# ESP12_mosfet_1117.net
KiCad netlist of a schematic drawn in EAGLE
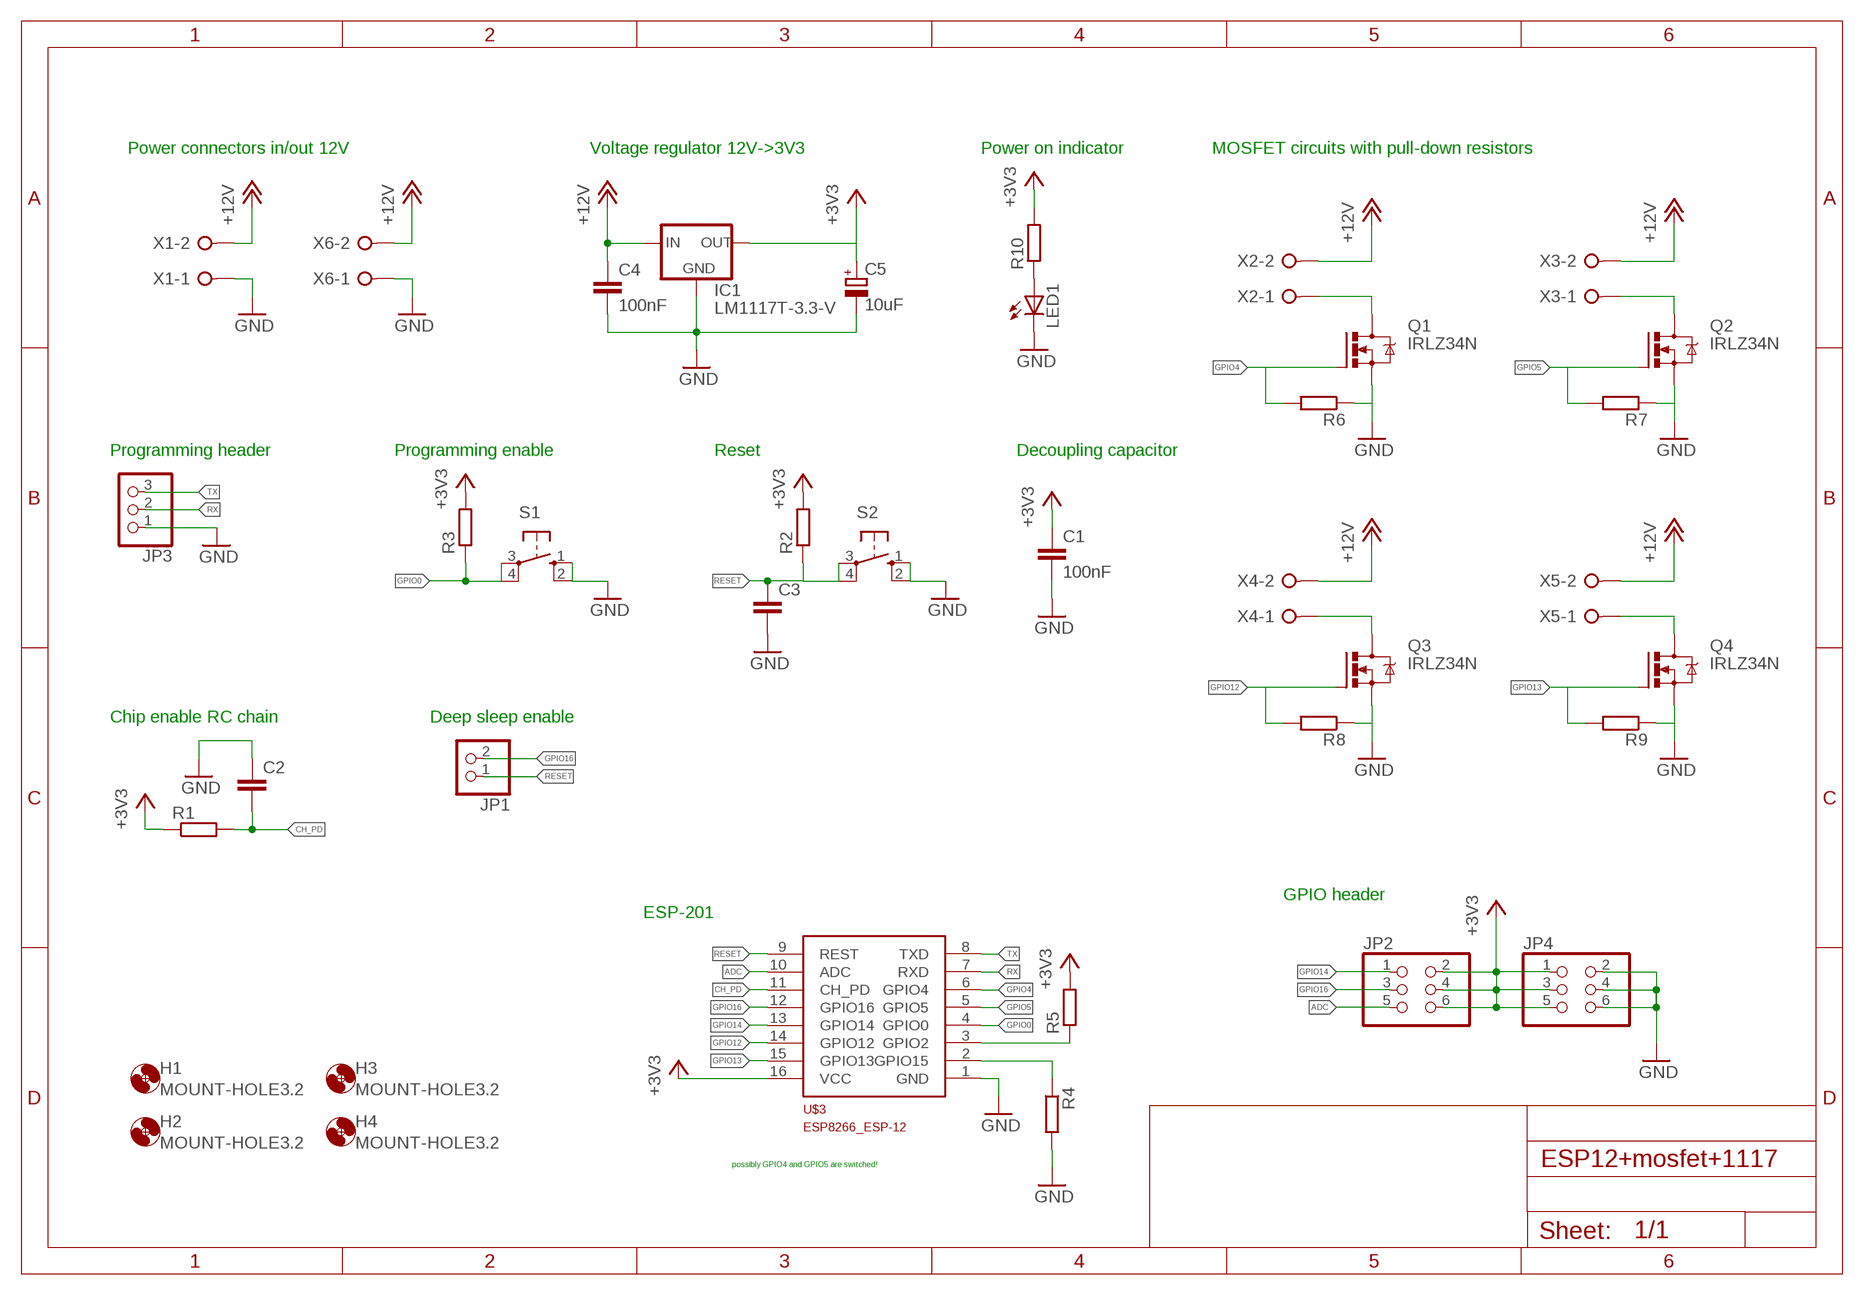
[diagram p0: schematic, sheet 1]

(export (version "E")
  (design (tool "Eeschema 10.0.6"))
  (components
    (comp (ref "C1")
      (value "100nF")
      (footprint "eagle-import:C0805")
      (libsource (lib "eagle-import") (part "C-EUC0805"))
    )
    (comp (ref "C2")
      (value "C-EUC0805")
      (footprint "eagle-import:C0805")
      (libsource (lib "eagle-import") (part "C-EUC0805"))
    )
    (comp (ref "C3")
      (value "C-EUC0805")
      (footprint "eagle-import:C0805")
      (libsource (lib "eagle-import") (part "C-EUC0805"))
    )
    (comp (ref "C4")
      (value "100nF")
      (footprint "eagle-import:C0805")
      (libsource (lib "eagle-import") (part "C-EUC0805"))
    )
    (comp (ref "C5")
      (value "10uF")
      (footprint "eagle-import:E2-4")
      (libsource (lib "eagle-import") (part "CPOL-EUE2-4"))
    )
    (comp (ref "H1")
      (value "MOUNT-HOLE3.2")
      (footprint "eagle-import:3,2")
      (libsource (lib "eagle-import") (part "MOUNT-HOLE3.2"))
    )
    (comp (ref "H2")
      (value "MOUNT-HOLE3.2")
      (footprint "eagle-import:3,2")
      (libsource (lib "eagle-import") (part "MOUNT-HOLE3.2"))
    )
    (comp (ref "H3")
      (value "MOUNT-HOLE3.2")
      (footprint "eagle-import:3,2")
      (libsource (lib "eagle-import") (part "MOUNT-HOLE3.2"))
    )
    (comp (ref "H4")
      (value "MOUNT-HOLE3.2")
      (footprint "eagle-import:3,2")
      (libsource (lib "eagle-import") (part "MOUNT-HOLE3.2"))
    )
    (comp (ref "IC1")
      (value "LM1117T-3.3-V")
      (footprint "eagle-import:TO220V")
      (libsource (lib "eagle-import") (part "LM1117T--V3.3"))
    )
    (comp (ref "JP1")
      (value "PINHD-1X2")
      (footprint "eagle-import:1X02")
      (libsource (lib "eagle-import") (part "PINHD-1X2"))
    )
    (comp (ref "JP2")
      (value "PINHD-2X3")
      (footprint "eagle-import:2X03")
      (libsource (lib "eagle-import") (part "PINHD-2X3"))
    )
    (comp (ref "JP3")
      (value "PINHD-1X3")
      (footprint "eagle-import:1X03")
      (libsource (lib "eagle-import") (part "PINHD-1X3"))
    )
    (comp (ref "JP4")
      (value "PINHD-2X3")
      (footprint "eagle-import:2X03")
      (libsource (lib "eagle-import") (part "PINHD-2X3"))
    )
    (comp (ref "LED1")
      (value "LED3MM")
      (footprint "eagle-import:LED3MM")
      (libsource (lib "eagle-import") (part "LED3MM"))
    )
    (comp (ref "Q1")
      (value "IRLZ34N")
      (footprint "eagle-import:TO220BV")
      (libsource (lib "eagle-import") (part "IRLZ44ZTO220BV"))
    )
    (comp (ref "Q2")
      (value "IRLZ34N")
      (footprint "eagle-import:TO220BV")
      (libsource (lib "eagle-import") (part "IRLZ44ZTO220BV"))
    )
    (comp (ref "Q3")
      (value "IRLZ34N")
      (footprint "eagle-import:TO220BV")
      (libsource (lib "eagle-import") (part "IRLZ44ZTO220BV"))
    )
    (comp (ref "Q4")
      (value "IRLZ34N")
      (footprint "eagle-import:TO220BV")
      (libsource (lib "eagle-import") (part "IRLZ44ZTO220BV"))
    )
    (comp (ref "R1")
      (value "R-EU_R0805")
      (footprint "eagle-import:R0805")
      (libsource (lib "eagle-import") (part "R-EU_R0805"))
    )
    (comp (ref "R2")
      (value "R-EU_R0805")
      (footprint "eagle-import:R0805")
      (libsource (lib "eagle-import") (part "R-EU_R0805"))
    )
    (comp (ref "R3")
      (value "R-EU_R0805")
      (footprint "eagle-import:R0805")
      (libsource (lib "eagle-import") (part "R-EU_R0805"))
    )
    (comp (ref "R4")
      (value "R-EU_R0805")
      (footprint "eagle-import:R0805")
      (libsource (lib "eagle-import") (part "R-EU_R0805"))
    )
    (comp (ref "R5")
      (value "R-EU_R0805")
      (footprint "eagle-import:R0805")
      (libsource (lib "eagle-import") (part "R-EU_R0805"))
    )
    (comp (ref "R6")
      (value "R-EU_R0805")
      (footprint "eagle-import:R0805")
      (libsource (lib "eagle-import") (part "R-EU_R0805"))
    )
    (comp (ref "R7")
      (value "R-EU_R0805")
      (footprint "eagle-import:R0805")
      (libsource (lib "eagle-import") (part "R-EU_R0805"))
    )
    (comp (ref "R8")
      (value "R-EU_R0805")
      (footprint "eagle-import:R0805")
      (libsource (lib "eagle-import") (part "R-EU_R0805"))
    )
    (comp (ref "R9")
      (value "R-EU_R0805")
      (footprint "eagle-import:R0805")
      (libsource (lib "eagle-import") (part "R-EU_R0805"))
    )
    (comp (ref "R10")
      (value "R-EU_0207/10")
      (footprint "eagle-import:0207_10")
      (libsource (lib "eagle-import") (part "R-EU_0207/10"))
    )
    (comp (ref "S1")
      (value "10-XX")
      (footprint "eagle-import:B3F-10XX")
      (fields (field (name "MPN") "B3F-1000"))
      (libsource (lib "eagle-import") (part "10-XX"))
    )
    (comp (ref "S2")
      (value "10-XX")
      (footprint "eagle-import:B3F-10XX")
      (fields (field (name "MPN") "B3F-1000"))
      (libsource (lib "eagle-import") (part "10-XX"))
    )
    (comp (ref "U$3")
      (value "ESP8266_ESP-12")
      (footprint "eagle-import:ESP8266-ESP12")
      (libsource (lib "eagle-import") (part "ESP8266_ESP-12"))
    )
    (comp (ref "X1")
      (value "W237-02P")
      (footprint "eagle-import:W237-132")
      (libsource (lib "eagle-import") (part "W237-02P"))
    )
    (comp (ref "X2")
      (value "W237-02P")
      (footprint "eagle-import:W237-132")
      (libsource (lib "eagle-import") (part "W237-02P"))
    )
    (comp (ref "X3")
      (value "W237-02P")
      (footprint "eagle-import:W237-132")
      (libsource (lib "eagle-import") (part "W237-02P"))
    )
    (comp (ref "X4")
      (value "W237-02P")
      (footprint "eagle-import:W237-132")
      (libsource (lib "eagle-import") (part "W237-02P"))
    )
    (comp (ref "X5")
      (value "W237-02P")
      (footprint "eagle-import:W237-132")
      (libsource (lib "eagle-import") (part "W237-02P"))
    )
    (comp (ref "X6")
      (value "W237-02P")
      (footprint "eagle-import:W237-132")
      (libsource (lib "eagle-import") (part "W237-02P"))
    )
  )
  (nets
    (net (code "1") (name "+3V3") (class "Default")
      (node (ref "C1") (pin "1") (pinfunction "1_1") (pintype "passive"))
      (node (ref "C5") (pin "+") (pinfunction "+_+") (pintype "passive"))
      (node (ref "IC1") (pin "2") (pinfunction "OUT_2") (pintype "passive"))
      (node (ref "JP2") (pin "2") (pinfunction "2_2") (pintype "passive"))
      (node (ref "JP2") (pin "4") (pinfunction "4_4") (pintype "passive"))
      (node (ref "JP2") (pin "6") (pinfunction "6_6") (pintype "passive"))
      (node (ref "JP4") (pin "1") (pinfunction "1_1") (pintype "passive"))
      (node (ref "JP4") (pin "3") (pinfunction "3_3") (pintype "passive"))
      (node (ref "JP4") (pin "5") (pinfunction "5_5") (pintype "passive"))
      (node (ref "R1") (pin "1") (pinfunction "1_1") (pintype "passive"))
      (node (ref "R10") (pin "2") (pinfunction "2_2") (pintype "passive"))
      (node (ref "R2") (pin "2") (pinfunction "2_2") (pintype "passive"))
      (node (ref "R3") (pin "2") (pinfunction "2_2") (pintype "passive"))
      (node (ref "R5") (pin "2") (pinfunction "2_2") (pintype "passive"))
      (node (ref "U$3") (pin "16") (pinfunction "VCC_16") (pintype "bidirectional"))
    )
    (net (code "2") (name "+12V") (class "Default")
      (node (ref "C4") (pin "1") (pinfunction "1_1") (pintype "passive"))
      (node (ref "IC1") (pin "3") (pinfunction "IN_3") (pintype "input"))
      (node (ref "X1") (pin "2") (pinfunction "KL_2") (pintype "passive"))
      (node (ref "X2") (pin "2") (pinfunction "KL_2") (pintype "passive"))
      (node (ref "X3") (pin "2") (pinfunction "KL_2") (pintype "passive"))
      (node (ref "X4") (pin "2") (pinfunction "KL_2") (pintype "passive"))
      (node (ref "X5") (pin "2") (pinfunction "KL_2") (pintype "passive"))
      (node (ref "X6") (pin "2") (pinfunction "KL_2") (pintype "passive"))
    )
    (net (code "3") (name "ADC") (class "Default")
      (node (ref "JP2") (pin "5") (pinfunction "5_5") (pintype "passive"))
      (node (ref "U$3") (pin "10") (pinfunction "ADC_10") (pintype "bidirectional"))
    )
    (net (code "4") (name "CH_PD") (class "Default")
      (node (ref "C2") (pin "2") (pinfunction "2_2") (pintype "passive"))
      (node (ref "R1") (pin "2") (pinfunction "2_2") (pintype "passive"))
      (node (ref "U$3") (pin "11") (pinfunction "CH_PD_11") (pintype "bidirectional"))
    )
    (net (code "5") (name "GND") (class "Default")
      (node (ref "C1") (pin "2") (pinfunction "2_2") (pintype "passive"))
      (node (ref "C2") (pin "1") (pinfunction "1_1") (pintype "passive"))
      (node (ref "C3") (pin "2") (pinfunction "2_2") (pintype "passive"))
      (node (ref "C4") (pin "2") (pinfunction "2_2") (pintype "passive"))
      (node (ref "C5") (pin "-") (pinfunction "-_-") (pintype "passive"))
      (node (ref "IC1") (pin "1") (pinfunction "GND_1") (pintype "input"))
      (node (ref "JP3") (pin "1") (pinfunction "1_1") (pintype "passive"))
      (node (ref "JP4") (pin "2") (pinfunction "2_2") (pintype "passive"))
      (node (ref "JP4") (pin "4") (pinfunction "4_4") (pintype "passive"))
      (node (ref "JP4") (pin "6") (pinfunction "6_6") (pintype "passive"))
      (node (ref "LED1") (pin "K") (pinfunction "C_K") (pintype "passive"))
      (node (ref "Q1") (pin "S") (pinfunction "S_S") (pintype "passive"))
      (node (ref "Q2") (pin "S") (pinfunction "S_S") (pintype "passive"))
      (node (ref "Q3") (pin "S") (pinfunction "S_S") (pintype "passive"))
      (node (ref "Q4") (pin "S") (pinfunction "S_S") (pintype "passive"))
      (node (ref "R4") (pin "2") (pinfunction "2_2") (pintype "passive"))
      (node (ref "R6") (pin "1") (pinfunction "1_1") (pintype "passive"))
      (node (ref "R7") (pin "1") (pinfunction "1_1") (pintype "passive"))
      (node (ref "R8") (pin "1") (pinfunction "1_1") (pintype "passive"))
      (node (ref "R9") (pin "1") (pinfunction "1_1") (pintype "passive"))
      (node (ref "S1") (pin "1") (pinfunction "S_1") (pintype "passive"))
      (node (ref "S1") (pin "2") (pinfunction "S1_2") (pintype "passive"))
      (node (ref "S2") (pin "1") (pinfunction "S_1") (pintype "passive"))
      (node (ref "S2") (pin "2") (pinfunction "S1_2") (pintype "passive"))
      (node (ref "U$3") (pin "1") (pinfunction "GND_1") (pintype "bidirectional"))
      (node (ref "X1") (pin "1") (pinfunction "KL_1") (pintype "passive"))
      (node (ref "X6") (pin "1") (pinfunction "KL_1") (pintype "passive"))
    )
    (net (code "6") (name "GPIO0") (class "Default")
      (node (ref "R3") (pin "1") (pinfunction "1_1") (pintype "passive"))
      (node (ref "S1") (pin "3") (pinfunction "P_3") (pintype "passive"))
      (node (ref "S1") (pin "4") (pinfunction "P1_4") (pintype "passive"))
      (node (ref "U$3") (pin "4") (pinfunction "GPIO0_4") (pintype "bidirectional"))
    )
    (net (code "7") (name "GPIO4") (class "Default")
      (node (ref "Q1") (pin "G") (pinfunction "G_G") (pintype "passive"))
      (node (ref "R6") (pin "2") (pinfunction "2_2") (pintype "passive"))
      (node (ref "U$3") (pin "6") (pinfunction "GPIO4_6") (pintype "bidirectional"))
    )
    (net (code "8") (name "GPIO5") (class "Default")
      (node (ref "Q2") (pin "G") (pinfunction "G_G") (pintype "passive"))
      (node (ref "R7") (pin "2") (pinfunction "2_2") (pintype "passive"))
      (node (ref "U$3") (pin "5") (pinfunction "GPIO5_5") (pintype "bidirectional"))
    )
    (net (code "9") (name "GPIO12") (class "Default")
      (node (ref "Q3") (pin "G") (pinfunction "G_G") (pintype "passive"))
      (node (ref "R8") (pin "2") (pinfunction "2_2") (pintype "passive"))
      (node (ref "U$3") (pin "14") (pinfunction "GPIO12_14") (pintype "bidirectional"))
    )
    (net (code "10") (name "GPIO13") (class "Default")
      (node (ref "Q4") (pin "G") (pinfunction "G_G") (pintype "passive"))
      (node (ref "R9") (pin "2") (pinfunction "2_2") (pintype "passive"))
      (node (ref "U$3") (pin "15") (pinfunction "GPIO13_15") (pintype "bidirectional"))
    )
    (net (code "11") (name "GPIO14") (class "Default")
      (node (ref "JP2") (pin "1") (pinfunction "1_1") (pintype "passive"))
      (node (ref "U$3") (pin "13") (pinfunction "GPIO14_13") (pintype "bidirectional"))
    )
    (net (code "12") (name "GPIO16") (class "Default")
      (node (ref "JP1") (pin "2") (pinfunction "2_2") (pintype "passive"))
      (node (ref "JP2") (pin "3") (pinfunction "3_3") (pintype "passive"))
      (node (ref "U$3") (pin "12") (pinfunction "GPIO16_12") (pintype "bidirectional"))
    )
    (net (code "13") (name "Net-(LED1-PadA)") (class "Default")
      (node (ref "LED1") (pin "A") (pinfunction "A_A") (pintype "passive"))
      (node (ref "R10") (pin "1") (pinfunction "1_1") (pintype "passive"))
    )
    (net (code "14") (name "Net-(U$3-GPIO2)") (class "Default")
      (node (ref "R5") (pin "1") (pinfunction "1_1") (pintype "passive"))
      (node (ref "U$3") (pin "3") (pinfunction "GPIO2_3") (pintype "bidirectional"))
    )
    (net (code "15") (name "Net-(U$3-GPIO15)") (class "Default")
      (node (ref "R4") (pin "1") (pinfunction "1_1") (pintype "passive"))
      (node (ref "U$3") (pin "2") (pinfunction "GPIO15_2") (pintype "bidirectional"))
    )
    (net (code "16") (name "Net-(X2A-KL)") (class "Default")
      (node (ref "Q1") (pin "D") (pinfunction "D_D") (pintype "passive"))
      (node (ref "X2") (pin "1") (pinfunction "KL_1") (pintype "passive"))
    )
    (net (code "17") (name "Net-(X3A-KL)") (class "Default")
      (node (ref "Q2") (pin "D") (pinfunction "D_D") (pintype "passive"))
      (node (ref "X3") (pin "1") (pinfunction "KL_1") (pintype "passive"))
    )
    (net (code "18") (name "Net-(X4A-KL)") (class "Default")
      (node (ref "Q3") (pin "D") (pinfunction "D_D") (pintype "passive"))
      (node (ref "X4") (pin "1") (pinfunction "KL_1") (pintype "passive"))
    )
    (net (code "19") (name "Net-(X5A-KL)") (class "Default")
      (node (ref "Q4") (pin "D") (pinfunction "D_D") (pintype "passive"))
      (node (ref "X5") (pin "1") (pinfunction "KL_1") (pintype "passive"))
    )
    (net (code "20") (name "RESET") (class "Default")
      (node (ref "C3") (pin "1") (pinfunction "1_1") (pintype "passive"))
      (node (ref "JP1") (pin "1") (pinfunction "1_1") (pintype "passive"))
      (node (ref "R2") (pin "1") (pinfunction "1_1") (pintype "passive"))
      (node (ref "S2") (pin "3") (pinfunction "P_3") (pintype "passive"))
      (node (ref "S2") (pin "4") (pinfunction "P1_4") (pintype "passive"))
      (node (ref "U$3") (pin "9") (pinfunction "REST_9") (pintype "bidirectional"))
    )
    (net (code "21") (name "RX") (class "Default")
      (node (ref "JP3") (pin "2") (pinfunction "2_2") (pintype "passive"))
      (node (ref "U$3") (pin "7") (pinfunction "RXD_7") (pintype "bidirectional"))
    )
    (net (code "22") (name "TX") (class "Default")
      (node (ref "JP3") (pin "3") (pinfunction "3_3") (pintype "passive"))
      (node (ref "U$3") (pin "8") (pinfunction "TXD_8") (pintype "bidirectional"))
    )
  )
)
